# Traffic_Lights_schematic.net
KiCad netlist of a schematic drawn in EAGLE
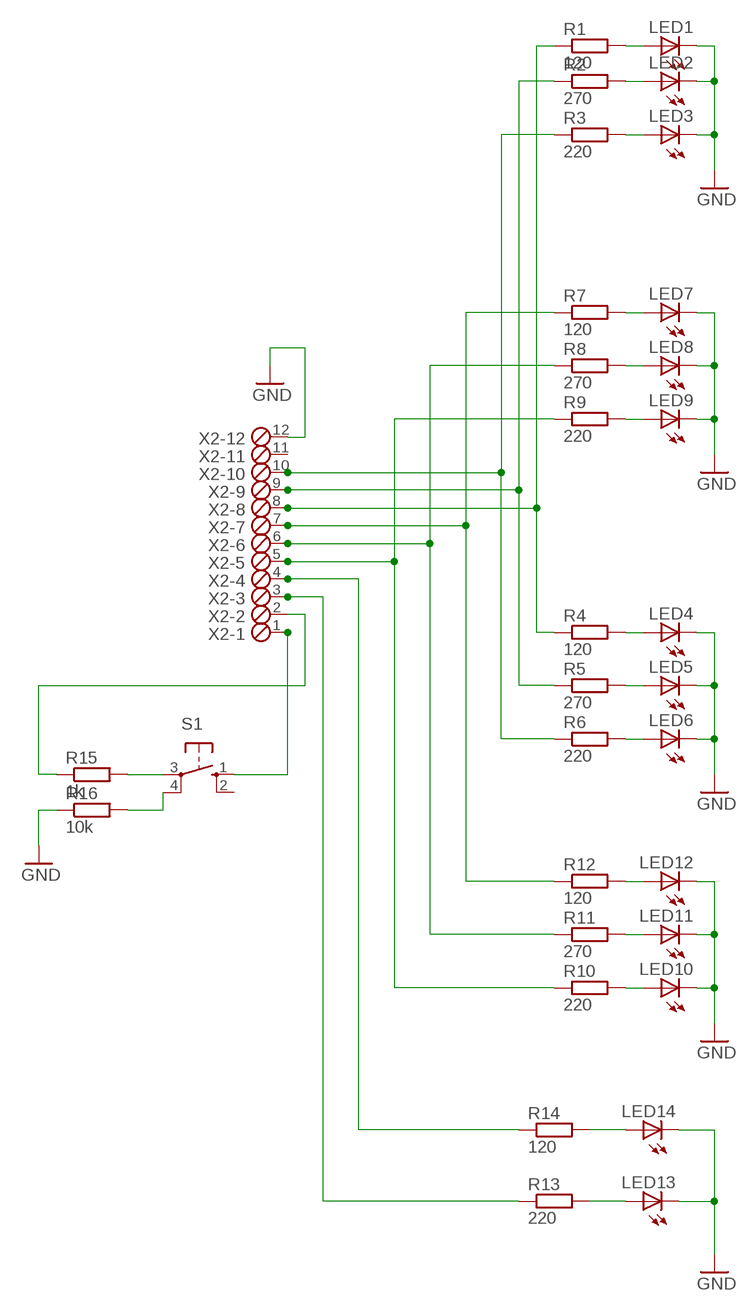
[diagram p0: schematic, sheet 1]

(export (version "E")
  (design (tool "Eeschema 10.0.6"))
  (components
    (comp (ref "LED1")
      (value "LED5MM")
      (footprint "eagle-import:LED5MM")
      (libsource (lib "eagle-import") (part "LED5MM"))
    )
    (comp (ref "LED2")
      (value "LED5MM")
      (footprint "eagle-import:LED5MM")
      (libsource (lib "eagle-import") (part "LED5MM"))
    )
    (comp (ref "LED3")
      (value "LED5MM")
      (footprint "eagle-import:LED5MM")
      (libsource (lib "eagle-import") (part "LED5MM"))
    )
    (comp (ref "LED4")
      (value "LED5MM")
      (footprint "eagle-import:LED5MM")
      (libsource (lib "eagle-import") (part "LED5MM"))
    )
    (comp (ref "LED5")
      (value "LED5MM")
      (footprint "eagle-import:LED5MM")
      (libsource (lib "eagle-import") (part "LED5MM"))
    )
    (comp (ref "LED6")
      (value "LED5MM")
      (footprint "eagle-import:LED5MM")
      (libsource (lib "eagle-import") (part "LED5MM"))
    )
    (comp (ref "LED7")
      (value "LED5MM")
      (footprint "eagle-import:LED5MM")
      (libsource (lib "eagle-import") (part "LED5MM"))
    )
    (comp (ref "LED8")
      (value "LED5MM")
      (footprint "eagle-import:LED5MM")
      (libsource (lib "eagle-import") (part "LED5MM"))
    )
    (comp (ref "LED9")
      (value "LED5MM")
      (footprint "eagle-import:LED5MM")
      (libsource (lib "eagle-import") (part "LED5MM"))
    )
    (comp (ref "LED10")
      (value "LED5MM")
      (footprint "eagle-import:LED5MM")
      (libsource (lib "eagle-import") (part "LED5MM"))
    )
    (comp (ref "LED11")
      (value "LED5MM")
      (footprint "eagle-import:LED5MM")
      (libsource (lib "eagle-import") (part "LED5MM"))
    )
    (comp (ref "LED12")
      (value "LED5MM")
      (footprint "eagle-import:LED5MM")
      (libsource (lib "eagle-import") (part "LED5MM"))
    )
    (comp (ref "LED13")
      (value "LED5MM")
      (footprint "eagle-import:LED5MM")
      (libsource (lib "eagle-import") (part "LED5MM"))
    )
    (comp (ref "LED14")
      (value "LED5MM")
      (footprint "eagle-import:LED5MM")
      (libsource (lib "eagle-import") (part "LED5MM"))
    )
    (comp (ref "R1")
      (value "120")
      (footprint "eagle-import:0207_7")
      (libsource (lib "eagle-import") (part "R-EU_0207/7"))
    )
    (comp (ref "R2")
      (value "270")
      (footprint "eagle-import:0207_7")
      (libsource (lib "eagle-import") (part "R-EU_0207/7"))
    )
    (comp (ref "R3")
      (value "220")
      (footprint "eagle-import:0207_7")
      (libsource (lib "eagle-import") (part "R-EU_0207/7"))
    )
    (comp (ref "R4")
      (value "120")
      (footprint "eagle-import:0207_7")
      (libsource (lib "eagle-import") (part "R-EU_0207/7"))
    )
    (comp (ref "R5")
      (value "270")
      (footprint "eagle-import:0207_7")
      (libsource (lib "eagle-import") (part "R-EU_0207/7"))
    )
    (comp (ref "R6")
      (value "220")
      (footprint "eagle-import:0207_7")
      (libsource (lib "eagle-import") (part "R-EU_0207/7"))
    )
    (comp (ref "R7")
      (value "120")
      (footprint "eagle-import:0207_7")
      (libsource (lib "eagle-import") (part "R-EU_0207/7"))
    )
    (comp (ref "R8")
      (value "270")
      (footprint "eagle-import:0207_7")
      (libsource (lib "eagle-import") (part "R-EU_0207/7"))
    )
    (comp (ref "R9")
      (value "220")
      (footprint "eagle-import:0207_7")
      (libsource (lib "eagle-import") (part "R-EU_0207/7"))
    )
    (comp (ref "R10")
      (value "220")
      (footprint "eagle-import:0207_7")
      (libsource (lib "eagle-import") (part "R-EU_0207/7"))
    )
    (comp (ref "R11")
      (value "270")
      (footprint "eagle-import:0207_7")
      (libsource (lib "eagle-import") (part "R-EU_0207/7"))
    )
    (comp (ref "R12")
      (value "120")
      (footprint "eagle-import:0207_7")
      (libsource (lib "eagle-import") (part "R-EU_0207/7"))
    )
    (comp (ref "R13")
      (value "220")
      (footprint "eagle-import:0207_7")
      (libsource (lib "eagle-import") (part "R-EU_0207/7"))
    )
    (comp (ref "R14")
      (value "120")
      (footprint "eagle-import:0207_7")
      (libsource (lib "eagle-import") (part "R-EU_0207/7"))
    )
    (comp (ref "R15")
      (value "1k")
      (footprint "eagle-import:0207_7")
      (libsource (lib "eagle-import") (part "R-EU_0207/7"))
    )
    (comp (ref "R16")
      (value "10k")
      (footprint "eagle-import:0207_7")
      (libsource (lib "eagle-import") (part "R-EU_0207/7"))
    )
    (comp (ref "S1")
      (value "10-XX")
      (footprint "eagle-import:B3F-10XX")
      (fields (field (name "MPN") "B3F-1000"))
      (libsource (lib "eagle-import") (part "10-XX"))
    )
    (comp (ref "X2")
      (value "MPT12")
      (footprint "eagle-import:12POL254")
      (libsource (lib "eagle-import") (part "MPT12"))
    )
  )
  (nets
    (net (code "1") (name "GND") (class "Default")
      (node (ref "LED1") (pin "K") (pinfunction "C_K") (pintype "passive"))
      (node (ref "LED10") (pin "K") (pinfunction "C_K") (pintype "passive"))
      (node (ref "LED11") (pin "K") (pinfunction "C_K") (pintype "passive"))
      (node (ref "LED12") (pin "K") (pinfunction "C_K") (pintype "passive"))
      (node (ref "LED13") (pin "K") (pinfunction "C_K") (pintype "passive"))
      (node (ref "LED14") (pin "K") (pinfunction "C_K") (pintype "passive"))
      (node (ref "LED2") (pin "K") (pinfunction "C_K") (pintype "passive"))
      (node (ref "LED3") (pin "K") (pinfunction "C_K") (pintype "passive"))
      (node (ref "LED4") (pin "K") (pinfunction "C_K") (pintype "passive"))
      (node (ref "LED5") (pin "K") (pinfunction "C_K") (pintype "passive"))
      (node (ref "LED6") (pin "K") (pinfunction "C_K") (pintype "passive"))
      (node (ref "LED7") (pin "K") (pinfunction "C_K") (pintype "passive"))
      (node (ref "LED8") (pin "K") (pinfunction "C_K") (pintype "passive"))
      (node (ref "LED9") (pin "K") (pinfunction "C_K") (pintype "passive"))
      (node (ref "R16") (pin "1") (pinfunction "1_1") (pintype "passive"))
      (node (ref "X2") (pin "12") (pinfunction "1_12") (pintype "passive"))
    )
    (net (code "2") (name "Net-(LED1-PadA)") (class "Default")
      (node (ref "LED1") (pin "A") (pinfunction "A_A") (pintype "passive"))
      (node (ref "R1") (pin "2") (pinfunction "2_2") (pintype "passive"))
    )
    (net (code "3") (name "Net-(LED2-PadA)") (class "Default")
      (node (ref "LED2") (pin "A") (pinfunction "A_A") (pintype "passive"))
      (node (ref "R2") (pin "2") (pinfunction "2_2") (pintype "passive"))
    )
    (net (code "4") (name "Net-(LED3-PadA)") (class "Default")
      (node (ref "LED3") (pin "A") (pinfunction "A_A") (pintype "passive"))
      (node (ref "R3") (pin "2") (pinfunction "2_2") (pintype "passive"))
    )
    (net (code "5") (name "Net-(LED4-PadA)") (class "Default")
      (node (ref "LED4") (pin "A") (pinfunction "A_A") (pintype "passive"))
      (node (ref "R4") (pin "2") (pinfunction "2_2") (pintype "passive"))
    )
    (net (code "6") (name "Net-(LED5-PadA)") (class "Default")
      (node (ref "LED5") (pin "A") (pinfunction "A_A") (pintype "passive"))
      (node (ref "R5") (pin "2") (pinfunction "2_2") (pintype "passive"))
    )
    (net (code "7") (name "Net-(LED6-PadA)") (class "Default")
      (node (ref "LED6") (pin "A") (pinfunction "A_A") (pintype "passive"))
      (node (ref "R6") (pin "2") (pinfunction "2_2") (pintype "passive"))
    )
    (net (code "8") (name "Net-(LED7-PadA)") (class "Default")
      (node (ref "LED7") (pin "A") (pinfunction "A_A") (pintype "passive"))
      (node (ref "R7") (pin "2") (pinfunction "2_2") (pintype "passive"))
    )
    (net (code "9") (name "Net-(LED8-PadA)") (class "Default")
      (node (ref "LED8") (pin "A") (pinfunction "A_A") (pintype "passive"))
      (node (ref "R8") (pin "2") (pinfunction "2_2") (pintype "passive"))
    )
    (net (code "10") (name "Net-(LED9-PadA)") (class "Default")
      (node (ref "LED9") (pin "A") (pinfunction "A_A") (pintype "passive"))
      (node (ref "R9") (pin "2") (pinfunction "2_2") (pintype "passive"))
    )
    (net (code "11") (name "Net-(LED10-PadA)") (class "Default")
      (node (ref "LED10") (pin "A") (pinfunction "A_A") (pintype "passive"))
      (node (ref "R10") (pin "2") (pinfunction "2_2") (pintype "passive"))
    )
    (net (code "12") (name "Net-(LED11-PadA)") (class "Default")
      (node (ref "LED11") (pin "A") (pinfunction "A_A") (pintype "passive"))
      (node (ref "R11") (pin "2") (pinfunction "2_2") (pintype "passive"))
    )
    (net (code "13") (name "Net-(LED12-PadA)") (class "Default")
      (node (ref "LED12") (pin "A") (pinfunction "A_A") (pintype "passive"))
      (node (ref "R12") (pin "2") (pinfunction "2_2") (pintype "passive"))
    )
    (net (code "14") (name "Net-(LED13-PadA)") (class "Default")
      (node (ref "LED13") (pin "A") (pinfunction "A_A") (pintype "passive"))
      (node (ref "R13") (pin "2") (pinfunction "2_2") (pintype "passive"))
    )
    (net (code "15") (name "Net-(LED14-PadA)") (class "Default")
      (node (ref "LED14") (pin "A") (pinfunction "A_A") (pintype "passive"))
      (node (ref "R14") (pin "2") (pinfunction "2_2") (pintype "passive"))
    )
    (net (code "16") (name "Net-(S1-P)") (class "Default")
      (node (ref "R15") (pin "2") (pinfunction "2_2") (pintype "passive"))
      (node (ref "S1") (pin "3") (pinfunction "P_3") (pintype "passive"))
    )
    (net (code "17") (name "Net-(S1-P1)") (class "Default")
      (node (ref "R16") (pin "2") (pinfunction "2_2") (pintype "passive"))
      (node (ref "S1") (pin "4") (pinfunction "P1_4") (pintype "passive"))
    )
    (net (code "18") (name "Net-(S1-S)") (class "Default")
      (node (ref "S1") (pin "1") (pinfunction "S_1") (pintype "passive"))
      (node (ref "X2") (pin "1") (pinfunction "1_1") (pintype "passive"))
    )
    (net (code "19") (name "Net-(X2B-1)") (class "Default")
      (node (ref "R3") (pin "1") (pinfunction "1_1") (pintype "passive"))
      (node (ref "R6") (pin "1") (pinfunction "1_1") (pintype "passive"))
      (node (ref "X2") (pin "10") (pinfunction "1_10") (pintype "passive"))
    )
    (net (code "20") (name "Net-(X2E-1)") (class "Default")
      (node (ref "R15") (pin "1") (pinfunction "1_1") (pintype "passive"))
      (node (ref "X2") (pin "2") (pinfunction "1_2") (pintype "passive"))
    )
    (net (code "21") (name "Net-(X2F-1)") (class "Default")
      (node (ref "R13") (pin "1") (pinfunction "1_1") (pintype "passive"))
      (node (ref "X2") (pin "3") (pinfunction "1_3") (pintype "passive"))
    )
    (net (code "22") (name "Net-(X2G-1)") (class "Default")
      (node (ref "R14") (pin "1") (pinfunction "1_1") (pintype "passive"))
      (node (ref "X2") (pin "4") (pinfunction "1_4") (pintype "passive"))
    )
    (net (code "23") (name "Net-(X2H-1)") (class "Default")
      (node (ref "R10") (pin "1") (pinfunction "1_1") (pintype "passive"))
      (node (ref "R9") (pin "1") (pinfunction "1_1") (pintype "passive"))
      (node (ref "X2") (pin "5") (pinfunction "1_5") (pintype "passive"))
    )
    (net (code "24") (name "Net-(X2I-1)") (class "Default")
      (node (ref "R11") (pin "1") (pinfunction "1_1") (pintype "passive"))
      (node (ref "R8") (pin "1") (pinfunction "1_1") (pintype "passive"))
      (node (ref "X2") (pin "6") (pinfunction "1_6") (pintype "passive"))
    )
    (net (code "25") (name "Net-(X2J-1)") (class "Default")
      (node (ref "R12") (pin "1") (pinfunction "1_1") (pintype "passive"))
      (node (ref "R7") (pin "1") (pinfunction "1_1") (pintype "passive"))
      (node (ref "X2") (pin "7") (pinfunction "1_7") (pintype "passive"))
    )
    (net (code "26") (name "Net-(X2K-1)") (class "Default")
      (node (ref "R1") (pin "1") (pinfunction "1_1") (pintype "passive"))
      (node (ref "R4") (pin "1") (pinfunction "1_1") (pintype "passive"))
      (node (ref "X2") (pin "8") (pinfunction "1_8") (pintype "passive"))
    )
    (net (code "27") (name "Net-(X2L-1)") (class "Default")
      (node (ref "R2") (pin "1") (pinfunction "1_1") (pintype "passive"))
      (node (ref "R5") (pin "1") (pinfunction "1_1") (pintype "passive"))
      (node (ref "X2") (pin "9") (pinfunction "1_9") (pintype "passive"))
    )
    (net (code "28") (name "unconnected-(S1-S1-Pad2)") (class "Default")
      (node (ref "S1") (pin "2") (pinfunction "S1_2") (pintype "passive"))
    )
    (net (code "29") (name "unconnected-(X2C-1-Pad11)") (class "Default")
      (node (ref "X2") (pin "11") (pinfunction "1_11") (pintype "passive"))
    )
  )
)
